# Stop_and_Go_555_PCB.net
KiCad netlist of a schematic drawn in EAGLE
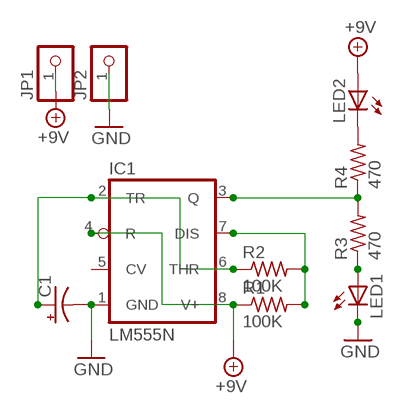
[diagram p0: schematic, sheet 1]

(export (version "E")
  (design (tool "Eeschema 10.0.6"))
  (components
    (comp (ref "C1")
      (value "CPOL-USE2.5-6")
      (footprint "eagle-import:E2,5-6")
      (libsource (lib "eagle-import") (part "CPOL-USE2.5-6"))
    )
    (comp (ref "IC1")
      (value "LM555N")
      (footprint "eagle-import:DIL08-ROUND")
      (libsource (lib "eagle-import") (part "555NLM"))
    )
    (comp (ref "JP1")
      (value "PINHD-1X1CB")
      (footprint "eagle-import:1X01-CLEANBIG")
      (libsource (lib "eagle-import") (part "PINHD-1X1CB"))
    )
    (comp (ref "JP2")
      (value "PINHD-1X1CB")
      (footprint "eagle-import:1X01-CLEANBIG")
      (libsource (lib "eagle-import") (part "PINHD-1X1CB"))
    )
    (comp (ref "LED1")
      (value "LED5MM")
      (footprint "eagle-import:LED5MM")
      (libsource (lib "eagle-import") (part "LED5MM"))
    )
    (comp (ref "LED2")
      (value "LED5MM")
      (footprint "eagle-import:LED5MM")
      (libsource (lib "eagle-import") (part "LED5MM"))
    )
    (comp (ref "R1")
      (value "100K")
      (footprint "eagle-import:0207_10")
      (libsource (lib "eagle-import") (part "R-US_0207/10"))
    )
    (comp (ref "R2")
      (value "100K")
      (footprint "eagle-import:0207_10")
      (libsource (lib "eagle-import") (part "R-US_0207/10"))
    )
    (comp (ref "R3")
      (value "470")
      (footprint "eagle-import:0207_10")
      (libsource (lib "eagle-import") (part "R-US_0207/10"))
    )
    (comp (ref "R4")
      (value "470")
      (footprint "eagle-import:0207_10")
      (libsource (lib "eagle-import") (part "R-US_0207/10"))
    )
  )
  (nets
    (net (code "1") (name "+9V") (class "Default")
      (node (ref "IC1") (pin "4") (pinfunction "R_4") (pintype "input"))
      (node (ref "IC1") (pin "8") (pinfunction "V+_8") (pintype "power_in"))
      (node (ref "JP1") (pin "1") (pinfunction "1_1") (pintype "passive"))
      (node (ref "LED2") (pin "A") (pinfunction "A_A") (pintype "passive"))
      (node (ref "R1") (pin "1") (pinfunction "1_1") (pintype "passive"))
    )
    (net (code "2") (name "GND") (class "Default")
      (node (ref "C1") (pin "-") (pinfunction "-_-") (pintype "passive"))
      (node (ref "IC1") (pin "1") (pinfunction "GND_1") (pintype "power_in"))
      (node (ref "JP2") (pin "1") (pinfunction "1_1") (pintype "passive"))
      (node (ref "LED1") (pin "K") (pinfunction "C_K") (pintype "passive"))
    )
    (net (code "3") (name "Net-(IC1-DIS)") (class "Default")
      (node (ref "IC1") (pin "7") (pinfunction "DIS_7") (pintype "input"))
      (node (ref "R1") (pin "2") (pinfunction "2_2") (pintype "passive"))
      (node (ref "R2") (pin "2") (pinfunction "2_2") (pintype "passive"))
    )
    (net (code "4") (name "Net-(IC1-Q)") (class "Default")
      (node (ref "IC1") (pin "3") (pinfunction "Q_3") (pintype "output"))
      (node (ref "R3") (pin "2") (pinfunction "2_2") (pintype "passive"))
      (node (ref "R4") (pin "1") (pinfunction "1_1") (pintype "passive"))
    )
    (net (code "5") (name "Net-(IC1-THR)") (class "Default")
      (node (ref "C1") (pin "+") (pinfunction "+_+") (pintype "passive"))
      (node (ref "IC1") (pin "2") (pinfunction "TR_2") (pintype "input"))
      (node (ref "IC1") (pin "6") (pinfunction "THR_6") (pintype "input"))
      (node (ref "R2") (pin "1") (pinfunction "1_1") (pintype "passive"))
    )
    (net (code "6") (name "Net-(LED1-PadA)") (class "Default")
      (node (ref "LED1") (pin "A") (pinfunction "A_A") (pintype "passive"))
      (node (ref "R3") (pin "1") (pinfunction "1_1") (pintype "passive"))
    )
    (net (code "7") (name "Net-(LED2-C)") (class "Default")
      (node (ref "LED2") (pin "K") (pinfunction "C_K") (pintype "passive"))
      (node (ref "R4") (pin "2") (pinfunction "2_2") (pintype "passive"))
    )
    (net (code "8") (name "unconnected-(IC1-CV-Pad5)") (class "Default")
      (node (ref "IC1") (pin "5") (pinfunction "CV_5") (pintype "input"))
    )
  )
)
